# ATTINYProgrammer.net
KiCad netlist of a schematic drawn in EAGLE
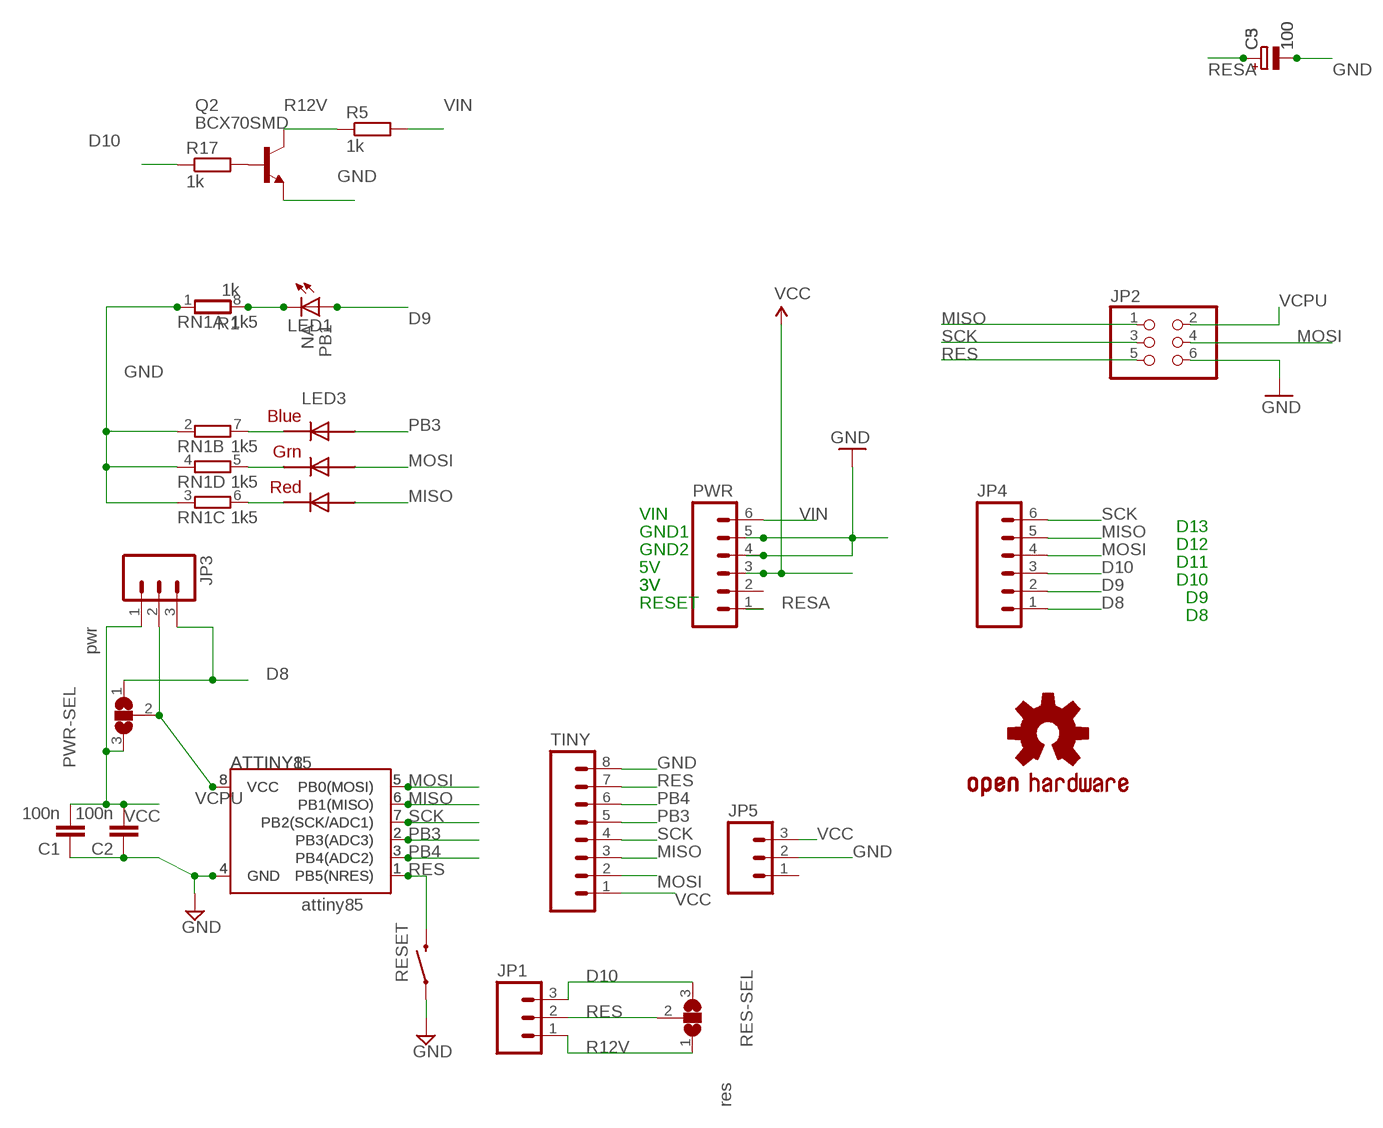
[diagram p0: schematic, sheet 1]

(export (version "E")
  (design (tool "Eeschema 10.0.6"))
  (components
    (comp (ref "ATTINY1")
      (value "ATTINY45")
      (footprint "eagle-import:SO08-EIAJ")
      (libsource (lib "eagle-import") (part "ATTINY45"))
    )
    (comp (ref "ATTINY85")
      (value "ATTINY45DIP8")
      (footprint "eagle-import:DIP08")
      (libsource (lib "eagle-import") (part "ATTINY45DIP8"))
    )
    (comp (ref "C1")
      (value "100n")
      (footprint "eagle-import:C0603")
      (libsource (lib "eagle-import") (part "C-EUC0603"))
    )
    (comp (ref "C2")
      (value "100n")
      (footprint "eagle-import:C025-024X044")
      (libsource (lib "eagle-import") (part "C-EU025-024X044"))
    )
    (comp (ref "C3")
      (value "100")
      (footprint "eagle-import:TT2D4")
      (libsource (lib "eagle-import") (part "CPOL-EUTT2D4"))
    )
    (comp (ref "C5")
      (value "100")
      (footprint "eagle-import:153CLV-0405")
      (libsource (lib "eagle-import") (part "CPOL-EU153CLV-0405"))
    )
    (comp (ref "JP1")
      (value "M03PTH")
      (footprint "eagle-import:1X03")
      (libsource (lib "eagle-import") (part "M03PTH"))
    )
    (comp (ref "JP2")
      (value "PINHD-2X3")
      (footprint "eagle-import:2X03")
      (libsource (lib "eagle-import") (part "PINHD-2X3"))
    )
    (comp (ref "JP3")
      (value "M03PTH")
      (footprint "eagle-import:1X03")
      (libsource (lib "eagle-import") (part "M03PTH"))
    )
    (comp (ref "JP4")
      (value "M06LOCK")
      (footprint "eagle-import:1X06_LOCK")
      (libsource (lib "eagle-import") (part "M06LOCK"))
    )
    (comp (ref "JP5")
      (value "M03LOCK")
      (footprint "eagle-import:1X03_LOCK")
      (libsource (lib "eagle-import") (part "M03LOCK"))
    )
    (comp (ref "LED1")
      (value "LED3MM")
      (footprint "eagle-import:LED3MM")
      (libsource (lib "eagle-import") (part "LED3MM"))
    )
    (comp (ref "LED3")
      (value "RGBLED5050")
      (footprint "eagle-import:RGBLED5050")
      (libsource (lib "eagle-import") (part "RGBLED5050"))
    )
    (comp (ref "PB1")
      (value "NA")
      (footprint "eagle-import:LED-0603")
      (libsource (lib "eagle-import") (part "LED0603DWS"))
    )
    (comp (ref "PWR")
      (value "M06LOCK")
      (footprint "eagle-import:1X06_LOCK")
      (libsource (lib "eagle-import") (part "M06LOCK"))
    )
    (comp (ref "PWR-SEL")
      (value "pwr")
      (footprint "eagle-import:SJ_2_SMALL")
      (libsource (lib "eagle-import") (part "SJ2W3"))
    )
    (comp (ref "Q2")
      (value "BCX70SMD")
      (footprint "eagle-import:SOT23")
      (libsource (lib "eagle-import") (part "BCX70SMD"))
    )
    (comp (ref "R1")
      (value "1k")
      (footprint "eagle-import:0204_5@1")
      (libsource (lib "eagle-import") (part "R-EU_0204/5"))
    )
    (comp (ref "R5")
      (value "1k")
      (footprint "eagle-import:R0603")
      (libsource (lib "eagle-import") (part "R-EU_R0603"))
    )
    (comp (ref "R17")
      (value "1k")
      (footprint "eagle-import:R0603")
      (libsource (lib "eagle-import") (part "R-EU_R0603"))
    )
    (comp (ref "RES-SEL")
      (value "res")
      (footprint "eagle-import:SJ_2_SMALL")
      (libsource (lib "eagle-import") (part "SJ2W3"))
    )
    (comp (ref "RESET")
      (value "SWITCH-MOMENTARY-2-SMD-1101NE")
      (footprint "eagle-import:TACTILE-SWITCH-1101NE")
      (libsource (lib "eagle-import") (part "SWITCH-MOMENTARY-2-SMD-1101NE"))
    )
    (comp (ref "RN1")
      (value "1k5")
      (footprint "eagle-import:0603-ARC")
      (fields (field (name "OC_FARNELL") "unknown") (field (name "OC_NEWARK") "unknown"))
      (libsource (lib "eagle-import") (part "4R-N0603-ARC"))
    )
    (comp (ref "TINY")
      (value "M08LOCK")
      (footprint "eagle-import:1X08_LOCK")
      (libsource (lib "eagle-import") (part "M08LOCK"))
    )
    (comp (ref "U$2")
      (value "OSHW-LOGOS")
      (footprint "eagle-import:OSHW-LOGO-S")
      (libsource (lib "eagle-import") (part "OSHW-LOGOS"))
    )
  )
  (nets
    (net (code "1") (name "/D8") (class "Default")
      (node (ref "JP3") (pin "3") (pinfunction "3_3") (pintype "passive"))
      (node (ref "JP4") (pin "1") (pinfunction "1_1") (pintype "passive"))
      (node (ref "PWR-SEL") (pin "1") (pinfunction "1_1") (pintype "passive"))
    )
    (net (code "2") (name "/D9") (class "Default")
      (node (ref "JP4") (pin "2") (pinfunction "2_2") (pintype "passive"))
      (node (ref "LED1") (pin "A") (pinfunction "A_A") (pintype "passive"))
      (node (ref "PB1") (pin "A") (pinfunction "A_A") (pintype "passive"))
    )
    (net (code "3") (name "/D10") (class "Default")
      (node (ref "JP1") (pin "3") (pinfunction "3_3") (pintype "passive"))
      (node (ref "JP4") (pin "3") (pinfunction "3_3") (pintype "passive"))
      (node (ref "R17") (pin "1") (pinfunction "1_1") (pintype "passive"))
      (node (ref "RES-SEL") (pin "3") (pinfunction "3_3") (pintype "passive"))
    )
    (net (code "4") (name "/MISO") (class "Default")
      (node (ref "ATTINY1") (pin "6") (pinfunction "PB1(MISO)_6") (pintype "bidirectional"))
      (node (ref "ATTINY85") (pin "6") (pinfunction "PB1(MISO)_6") (pintype "bidirectional"))
      (node (ref "JP2") (pin "1") (pinfunction "1_1") (pintype "passive"))
      (node (ref "JP4") (pin "5") (pinfunction "5_5") (pintype "passive"))
      (node (ref "LED3") (pin "2") (pinfunction "RED_A_2") (pintype "bidirectional"))
      (node (ref "TINY") (pin "3") (pinfunction "3_3") (pintype "passive"))
    )
    (net (code "5") (name "/MOSI") (class "Default")
      (node (ref "ATTINY1") (pin "5") (pinfunction "PB0(MOSI)_5") (pintype "bidirectional"))
      (node (ref "ATTINY85") (pin "5") (pinfunction "PB0(MOSI)_5") (pintype "bidirectional"))
      (node (ref "JP2") (pin "4") (pinfunction "4_4") (pintype "passive"))
      (node (ref "JP4") (pin "4") (pinfunction "4_4") (pintype "passive"))
      (node (ref "LED3") (pin "1") (pinfunction "GREEN_A_1") (pintype "bidirectional"))
      (node (ref "TINY") (pin "2") (pinfunction "2_2") (pintype "passive"))
    )
    (net (code "6") (name "/PB3") (class "Default")
      (node (ref "ATTINY1") (pin "2") (pinfunction "PB3(ADC3)_2") (pintype "bidirectional"))
      (node (ref "ATTINY85") (pin "2") (pinfunction "PB3(ADC3)_2") (pintype "bidirectional"))
      (node (ref "LED3") (pin "3") (pinfunction "BLUE_A_3") (pintype "bidirectional"))
      (node (ref "TINY") (pin "5") (pinfunction "5_5") (pintype "passive"))
    )
    (net (code "7") (name "/PB4") (class "Default")
      (node (ref "ATTINY1") (pin "3") (pinfunction "PB4(ADC2)_3") (pintype "bidirectional"))
      (node (ref "ATTINY85") (pin "3") (pinfunction "PB4(ADC2)_3") (pintype "bidirectional"))
      (node (ref "TINY") (pin "6") (pinfunction "6_6") (pintype "passive"))
    )
    (net (code "8") (name "/R12V") (class "Default")
      (node (ref "JP1") (pin "1") (pinfunction "1_1") (pintype "passive"))
      (node (ref "Q2") (pin "3") (pinfunction "C_3") (pintype "passive"))
      (node (ref "R5") (pin "1") (pinfunction "1_1") (pintype "passive"))
      (node (ref "RES-SEL") (pin "1") (pinfunction "1_1") (pintype "passive"))
    )
    (net (code "9") (name "/RES") (class "Default")
      (node (ref "ATTINY1") (pin "1") (pinfunction "PB5(NRES)_1") (pintype "bidirectional"))
      (node (ref "ATTINY85") (pin "1") (pinfunction "PB5(NRES)_1") (pintype "bidirectional"))
      (node (ref "JP1") (pin "2") (pinfunction "2_2") (pintype "passive"))
      (node (ref "JP2") (pin "5") (pinfunction "5_5") (pintype "passive"))
      (node (ref "RES-SEL") (pin "2") (pinfunction "2_2") (pintype "passive"))
      (node (ref "RESET") (pin "P$2") (pinfunction "2_P$2") (pintype "passive"))
      (node (ref "TINY") (pin "7") (pinfunction "7_7") (pintype "passive"))
    )
    (net (code "10") (name "/RESA") (class "Default")
      (node (ref "C3") (pin "+") (pinfunction "+_+") (pintype "passive"))
      (node (ref "C5") (pin "+") (pinfunction "+_+") (pintype "passive"))
      (node (ref "PWR") (pin "1") (pinfunction "1_1") (pintype "passive"))
    )
    (net (code "11") (name "/SCK") (class "Default")
      (node (ref "ATTINY1") (pin "7") (pinfunction "PB2(SCK/ADC1)_7") (pintype "bidirectional"))
      (node (ref "ATTINY85") (pin "7") (pinfunction "PB2(SCK/ADC1)_7") (pintype "bidirectional"))
      (node (ref "JP2") (pin "3") (pinfunction "3_3") (pintype "passive"))
      (node (ref "JP4") (pin "6") (pinfunction "6_6") (pintype "passive"))
      (node (ref "TINY") (pin "4") (pinfunction "4_4") (pintype "passive"))
    )
    (net (code "12") (name "/VCPU") (class "Default")
      (node (ref "ATTINY1") (pin "8") (pinfunction "VCC_8") (pintype "bidirectional"))
      (node (ref "ATTINY85") (pin "8") (pinfunction "VCC_8") (pintype "bidirectional"))
      (node (ref "JP2") (pin "2") (pinfunction "2_2") (pintype "passive"))
      (node (ref "JP3") (pin "2") (pinfunction "2_2") (pintype "passive"))
      (node (ref "PWR-SEL") (pin "2") (pinfunction "2_2") (pintype "passive"))
    )
    (net (code "13") (name "/VIN") (class "Default")
      (node (ref "PWR") (pin "6") (pinfunction "6_6") (pintype "passive"))
      (node (ref "R5") (pin "2") (pinfunction "2_2") (pintype "passive"))
    )
    (net (code "14") (name "GND") (class "Default")
      (node (ref "ATTINY1") (pin "4") (pinfunction "GND_4") (pintype "bidirectional"))
      (node (ref "ATTINY85") (pin "4") (pinfunction "GND_4") (pintype "bidirectional"))
      (node (ref "C1") (pin "1") (pinfunction "1_1") (pintype "passive"))
      (node (ref "C2") (pin "1") (pinfunction "1_1") (pintype "passive"))
      (node (ref "C3") (pin "-") (pinfunction "-_-") (pintype "passive"))
      (node (ref "C5") (pin "-") (pinfunction "-_-") (pintype "passive"))
      (node (ref "JP2") (pin "6") (pinfunction "6_6") (pintype "passive"))
      (node (ref "JP5") (pin "2") (pinfunction "2_2") (pintype "passive"))
      (node (ref "PWR") (pin "4") (pinfunction "4_4") (pintype "passive"))
      (node (ref "PWR") (pin "5") (pinfunction "5_5") (pintype "passive"))
      (node (ref "Q2") (pin "2") (pinfunction "E_2") (pintype "passive"))
      (node (ref "R1") (pin "2") (pinfunction "2_2") (pintype "passive"))
      (node (ref "RESET") (pin "P$1") (pinfunction "1_P$1") (pintype "passive"))
      (node (ref "RN1") (pin "1") (pinfunction "1_1") (pintype "passive"))
      (node (ref "RN1") (pin "2") (pinfunction "1_2") (pintype "passive"))
      (node (ref "RN1") (pin "3") (pinfunction "1_3") (pintype "passive"))
      (node (ref "RN1") (pin "4") (pinfunction "1_4") (pintype "passive"))
      (node (ref "TINY") (pin "8") (pinfunction "8_8") (pintype "passive"))
    )
    (net (code "15") (name "Net-(LED1-C)") (class "Default")
      (node (ref "LED1") (pin "K") (pinfunction "C_K") (pintype "passive"))
      (node (ref "PB1") (pin "C") (pinfunction "C_C") (pintype "passive"))
      (node (ref "R1") (pin "1") (pinfunction "1_1") (pintype "passive"))
      (node (ref "RN1") (pin "8") (pinfunction "2_8") (pintype "passive"))
    )
    (net (code "16") (name "Net-(LED3-BLUE_C)") (class "Default")
      (node (ref "LED3") (pin "4") (pinfunction "BLUE_C_4") (pintype "bidirectional"))
      (node (ref "RN1") (pin "7") (pinfunction "2_7") (pintype "passive"))
    )
    (net (code "17") (name "Net-(LED3-GREEN_C)") (class "Default")
      (node (ref "LED3") (pin "6") (pinfunction "GREEN_C_6") (pintype "bidirectional"))
      (node (ref "RN1") (pin "5") (pinfunction "2_5") (pintype "passive"))
    )
    (net (code "18") (name "Net-(LED3-RED_C)") (class "Default")
      (node (ref "LED3") (pin "5") (pinfunction "RED_C_5") (pintype "bidirectional"))
      (node (ref "RN1") (pin "6") (pinfunction "2_6") (pintype "passive"))
    )
    (net (code "19") (name "Net-(Q2-B)") (class "Default")
      (node (ref "Q2") (pin "1") (pinfunction "B_1") (pintype "passive"))
      (node (ref "R17") (pin "2") (pinfunction "2_2") (pintype "passive"))
    )
    (net (code "20") (name "VCC") (class "Default")
      (node (ref "C1") (pin "2") (pinfunction "2_2") (pintype "passive"))
      (node (ref "C2") (pin "2") (pinfunction "2_2") (pintype "passive"))
      (node (ref "JP3") (pin "1") (pinfunction "1_1") (pintype "passive"))
      (node (ref "JP5") (pin "3") (pinfunction "3_3") (pintype "passive"))
      (node (ref "PWR") (pin "3") (pinfunction "3_3") (pintype "passive"))
      (node (ref "PWR-SEL") (pin "3") (pinfunction "3_3") (pintype "passive"))
      (node (ref "TINY") (pin "1") (pinfunction "1_1") (pintype "passive"))
    )
    (net (code "21") (name "unconnected-(JP5-Pad1)") (class "Default")
      (node (ref "JP5") (pin "1") (pinfunction "1_1") (pintype "passive"))
    )
    (net (code "22") (name "unconnected-(PWR-Pad2)") (class "Default")
      (node (ref "PWR") (pin "2") (pinfunction "2_2") (pintype "passive"))
    )
  )
)
